# REUN_468349_001_PSU_Board_Connectors.net
KiCad netlist of a schematic drawn in Altium Designer
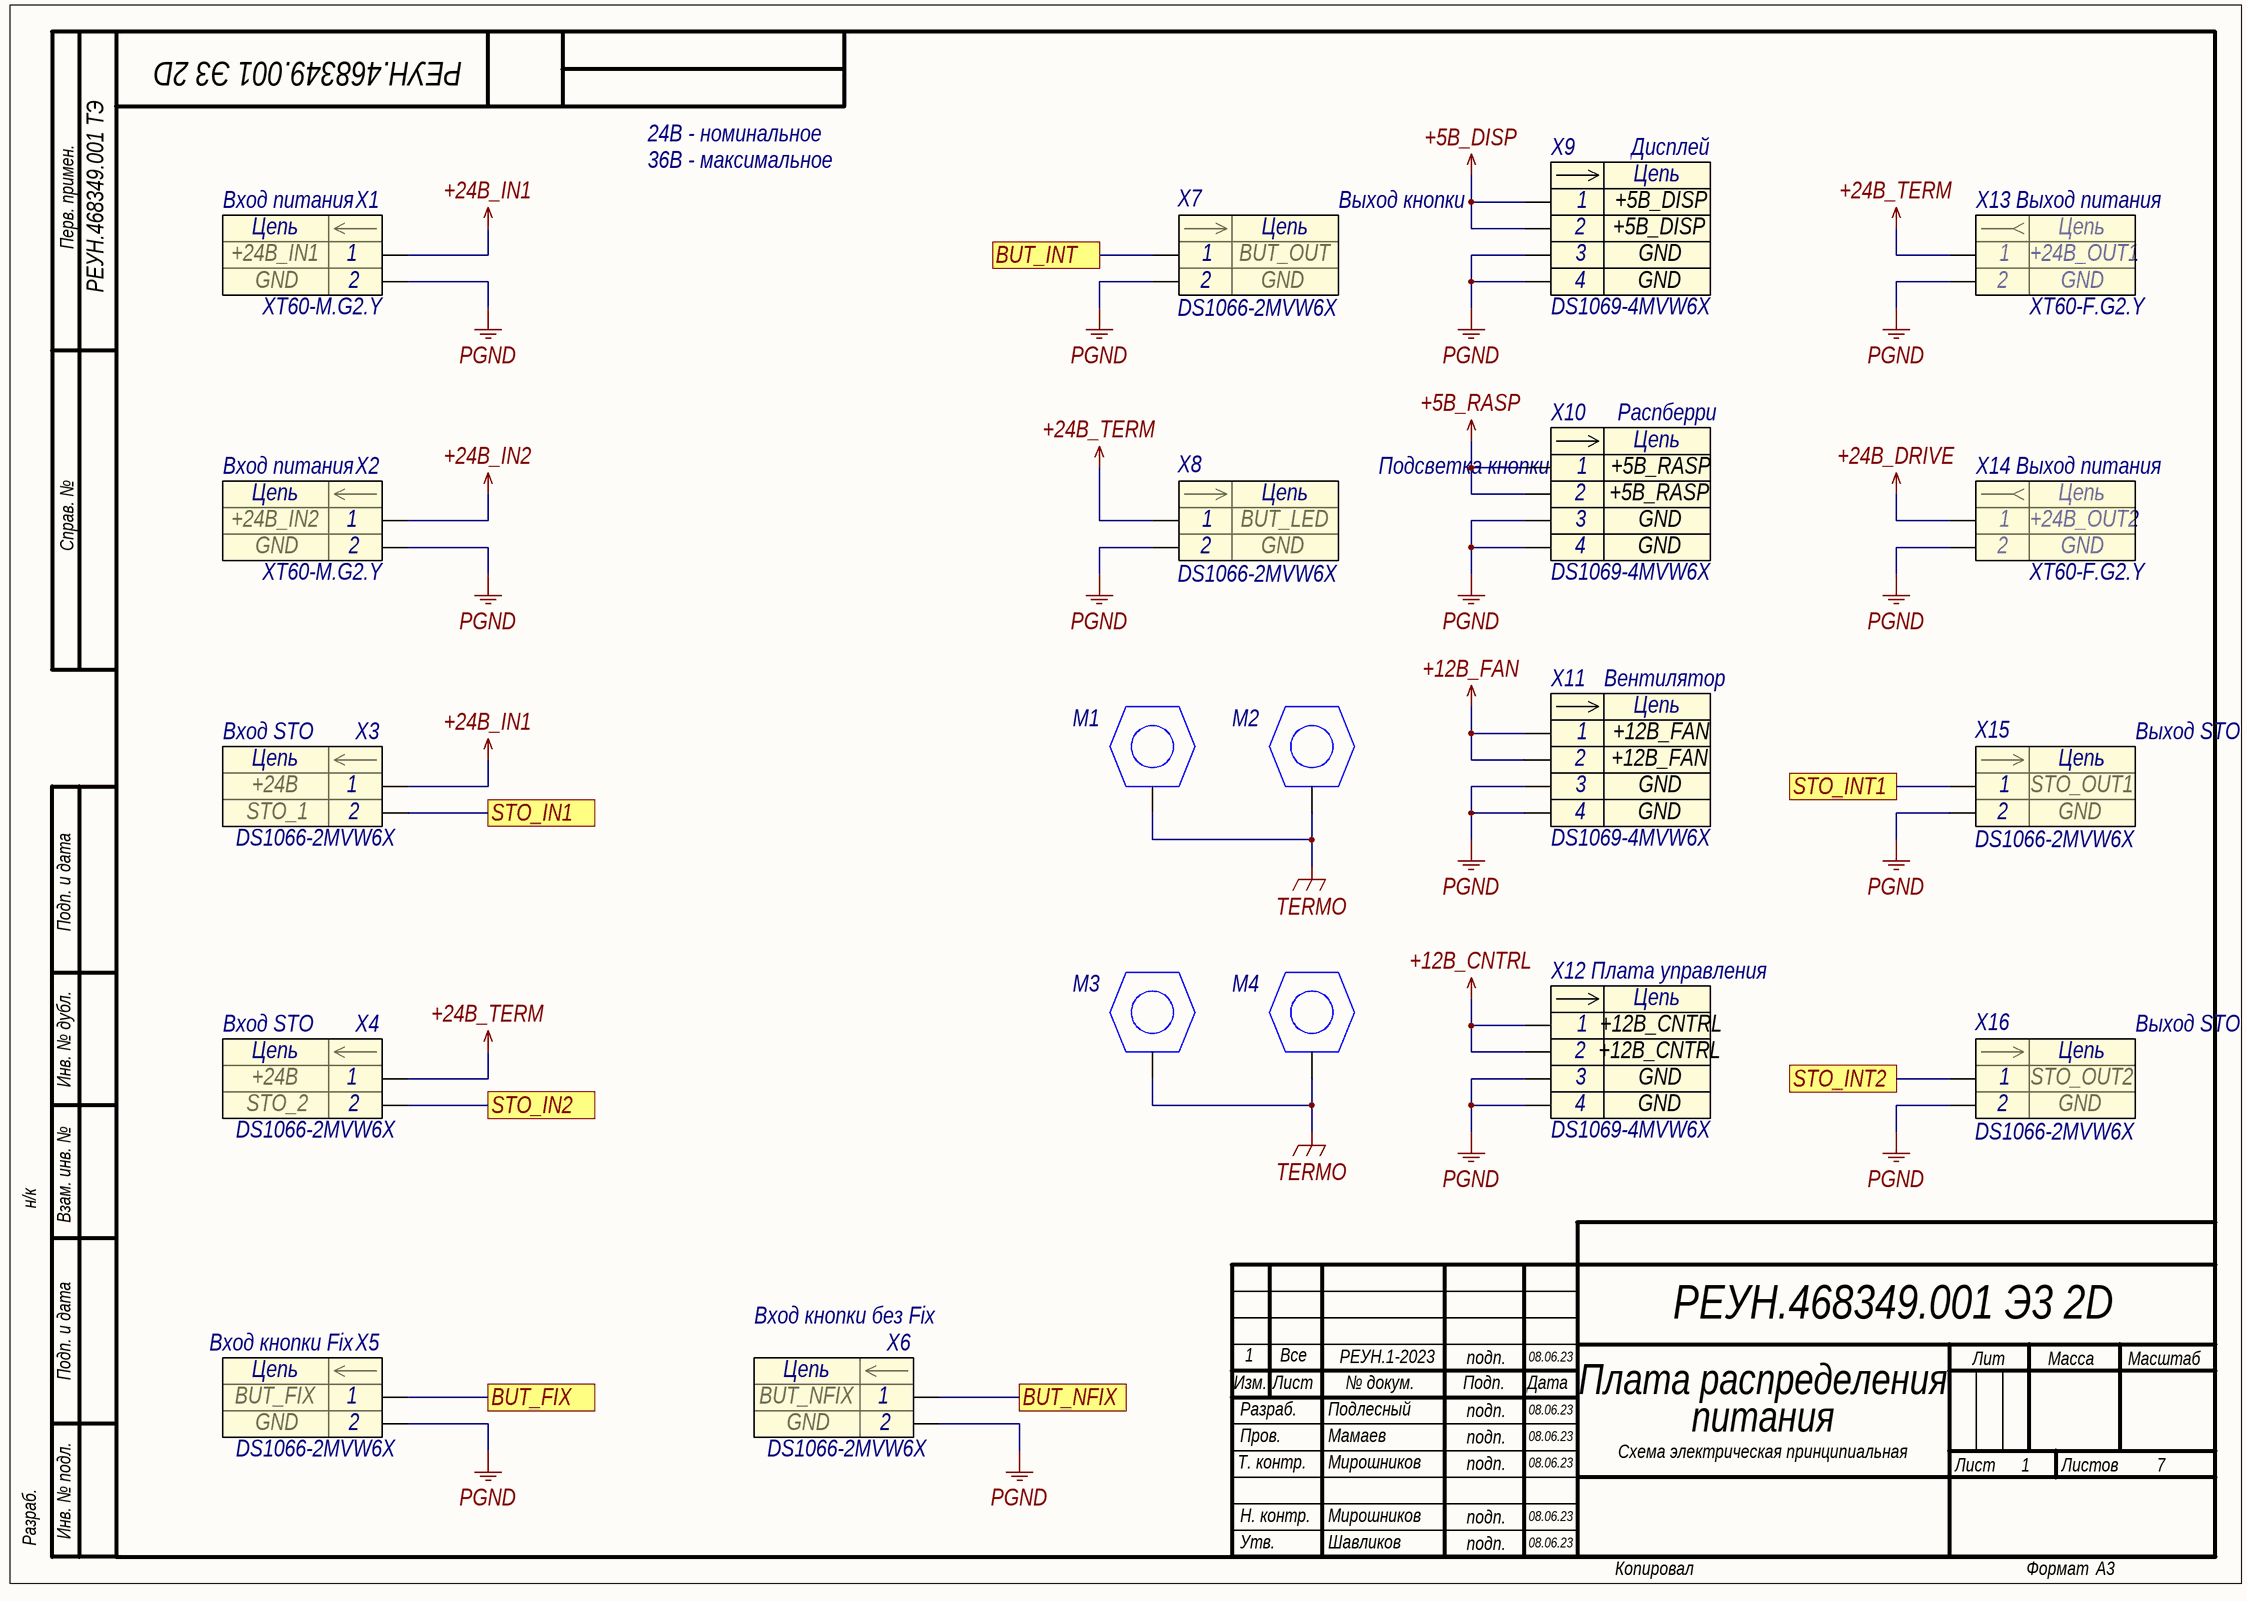
[diagram p0: REUN.468349.001_PSU_Board_Connectors.SchDoc]

(export (version "E")
  (design (tool "Eeschema 10.0.6"))
  (components
    (comp (ref "M1")
      (value "SCREW")
      (footprint "SCREW3.5")
      (libsource (lib "REUN.468349.001_PSU_Board") (part "SCREW"))
    )
    (comp (ref "M2")
      (value "SCREW")
      (footprint "SCREW3.5")
      (libsource (lib "REUN.468349.001_PSU_Board") (part "SCREW"))
    )
    (comp (ref "M3")
      (value "SCREW")
      (footprint "SCREW3.5")
      (libsource (lib "REUN.468349.001_PSU_Board") (part "SCREW"))
    )
    (comp (ref "M4")
      (value "SCREW")
      (footprint "SCREW3.5")
      (libsource (lib "REUN.468349.001_PSU_Board") (part "SCREW"))
    )
    (comp (ref "X1")
      (value "XT60-M.G2.Y")
      (footprint "XT60-M_TH")
      (description "Разъем - 2 конт. вилка")
      (libsource (lib "MOP44") (part "Header_2_plg"))
    )
    (comp (ref "X2")
      (value "XT60-M.G2.Y")
      (footprint "XT60-M_TH")
      (description "Разъем - 2 конт. вилка")
      (libsource (lib "MOP44") (part "Header_2_plg"))
    )
    (comp (ref "X3")
      (value "DS1066-2MVW6X")
      (footprint "MW-2M")
      (description "Разъем - 2 конт. вилка")
      (libsource (lib "MOP44") (part "Header_2_plg"))
    )
    (comp (ref "X4")
      (value "DS1066-2MVW6X")
      (footprint "MW-2M")
      (description "Разъем - 2 конт. вилка")
      (libsource (lib "MOP44") (part "Header_2_plg"))
    )
    (comp (ref "X5")
      (value "DS1066-2MVW6X")
      (footprint "MW-2M")
      (description "Разъем - 2 конт. вилка")
      (libsource (lib "MOP44") (part "Header_2_plg"))
    )
    (comp (ref "X6")
      (value "DS1066-2MVW6X")
      (footprint "MW-2M")
      (description "Разъем - 2 конт. вилка")
      (libsource (lib "MOP44") (part "Header_2_plg"))
    )
    (comp (ref "X7")
      (value "DS1066-2MVW6X")
      (footprint "MW-2M")
      (description "Разъем - 2 конт. вилка")
      (libsource (lib "") (part "Header_2_plg_1"))
    )
    (comp (ref "X8")
      (value "DS1066-2MVW6X")
      (footprint "MW-2M")
      (description "Разъем - 2 конт. вилка")
      (libsource (lib "") (part "Header_2_plg_1"))
    )
    (comp (ref "X9")
      (value "DS1069-4MVW6X")
      (footprint "CWF-4")
      (description "Разъем - 4 конт. вилка")
      (fields (field (name "PART NUMBER") "DS1069-4MVW6X"))
      (libsource (lib "MOP44") (part "Header_4_plg"))
    )
    (comp (ref "X10")
      (value "DS1069-4MVW6X")
      (footprint "CWF-4")
      (description "Разъем - 4 конт. вилка")
      (fields (field (name "PART NUMBER") "DS1069-4MVW6X"))
      (libsource (lib "MOP44") (part "Header_4_plg"))
    )
    (comp (ref "X11")
      (value "DS1069-4MVW6X")
      (footprint "CWF-4")
      (description "Разъем - 4 конт. вилка")
      (fields (field (name "PART NUMBER") "DS1069-4MVW6X"))
      (libsource (lib "MOP44") (part "Header_4_plg"))
    )
    (comp (ref "X12")
      (value "DS1069-4MVW6X")
      (footprint "CWF-4")
      (description "Разъем - 4 конт. вилка")
      (fields (field (name "PART NUMBER") "DS1069-4MVW6X"))
      (libsource (lib "MOP44") (part "Header_4_plg"))
    )
    (comp (ref "X13")
      (value "XT60-F.G2.Y")
      (footprint "XT60-F_TH")
      (description "Разъем - 2 конт. розетка")
      (libsource (lib "MOP44") (part "Header_2_sct"))
    )
    (comp (ref "X14")
      (value "XT60-F.G2.Y")
      (footprint "XT60-F_TH")
      (description "Разъем - 2 конт. розетка")
      (libsource (lib "MOP44") (part "Header_2_sct"))
    )
    (comp (ref "X15")
      (value "DS1066-2MVW6X")
      (footprint "MW-2M")
      (description "Разъем - 2 конт. вилка")
      (libsource (lib "") (part "Header_2_plg_1"))
    )
    (comp (ref "X16")
      (value "DS1066-2MVW6X")
      (footprint "MW-2M")
      (description "Разъем - 2 конт. вилка")
      (libsource (lib "") (part "Header_2_plg_1"))
    )
  )
  (nets
    (net (code "1") (name "+5B_DISP") (class "Default")
      (node (ref "X9") (pin "1") (pinfunction "1_1") (pintype "passive"))
      (node (ref "X9") (pin "2") (pinfunction "2_2") (pintype "passive"))
    )
    (net (code "2") (name "+5B_RASP") (class "Default")
      (node (ref "X10") (pin "1") (pinfunction "1_1") (pintype "passive"))
      (node (ref "X10") (pin "2") (pinfunction "2_2") (pintype "passive"))
    )
    (net (code "3") (name "+12B_CNTRL") (class "Default")
      (node (ref "X12") (pin "1") (pinfunction "1_1") (pintype "passive"))
      (node (ref "X12") (pin "2") (pinfunction "2_2") (pintype "passive"))
    )
    (net (code "4") (name "+12B_FAN") (class "Default")
      (node (ref "X11") (pin "1") (pinfunction "1_1") (pintype "passive"))
      (node (ref "X11") (pin "2") (pinfunction "2_2") (pintype "passive"))
    )
    (net (code "5") (name "+24B_DRIVE") (class "Default")
      (node (ref "X14") (pin "1") (pinfunction "1_1") (pintype "passive"))
    )
    (net (code "6") (name "+24B_IN1") (class "Default")
      (node (ref "X1") (pin "1") (pinfunction "1_1") (pintype "passive"))
      (node (ref "X3") (pin "1") (pinfunction "1_1") (pintype "passive"))
    )
    (net (code "7") (name "+24B_IN2") (class "Default")
      (node (ref "X2") (pin "1") (pinfunction "1_1") (pintype "passive"))
    )
    (net (code "8") (name "+24B_TERM") (class "Default")
      (node (ref "X13") (pin "1") (pinfunction "1_1") (pintype "passive"))
      (node (ref "X4") (pin "1") (pinfunction "1_1") (pintype "passive"))
      (node (ref "X8") (pin "1") (pinfunction "1_1") (pintype "passive"))
    )
    (net (code "9") (name "/BUT_FIX") (class "Default")
      (node (ref "X5") (pin "1") (pinfunction "1_1") (pintype "passive"))
    )
    (net (code "10") (name "/BUT_INT") (class "Default")
      (node (ref "X7") (pin "1") (pinfunction "1_1") (pintype "passive"))
    )
    (net (code "11") (name "/BUT_NFIX") (class "Default")
      (node (ref "X6") (pin "1") (pinfunction "1_1") (pintype "passive"))
    )
    (net (code "12") (name "/STO_IN1") (class "Default")
      (node (ref "X3") (pin "2") (pinfunction "2_2") (pintype "passive"))
    )
    (net (code "13") (name "/STO_IN2") (class "Default")
      (node (ref "X4") (pin "2") (pinfunction "2_2") (pintype "passive"))
    )
    (net (code "14") (name "/STO_INT1") (class "Default")
      (node (ref "X15") (pin "1") (pinfunction "1_1") (pintype "passive"))
    )
    (net (code "15") (name "/STO_INT2") (class "Default")
      (node (ref "X16") (pin "1") (pinfunction "1_1") (pintype "passive"))
    )
    (net (code "16") (name "PGND") (class "Default")
      (node (ref "X1") (pin "2") (pinfunction "2_2") (pintype "passive"))
      (node (ref "X10") (pin "3") (pinfunction "3_3") (pintype "passive"))
      (node (ref "X10") (pin "4") (pinfunction "4_4") (pintype "passive"))
      (node (ref "X11") (pin "3") (pinfunction "3_3") (pintype "passive"))
      (node (ref "X11") (pin "4") (pinfunction "4_4") (pintype "passive"))
      (node (ref "X12") (pin "3") (pinfunction "3_3") (pintype "passive"))
      (node (ref "X12") (pin "4") (pinfunction "4_4") (pintype "passive"))
      (node (ref "X13") (pin "2") (pinfunction "2_2") (pintype "passive"))
      (node (ref "X14") (pin "2") (pinfunction "2_2") (pintype "passive"))
      (node (ref "X15") (pin "2") (pinfunction "2_2") (pintype "passive"))
      (node (ref "X16") (pin "2") (pinfunction "2_2") (pintype "passive"))
      (node (ref "X2") (pin "2") (pinfunction "2_2") (pintype "passive"))
      (node (ref "X5") (pin "2") (pinfunction "2_2") (pintype "passive"))
      (node (ref "X6") (pin "2") (pinfunction "2_2") (pintype "passive"))
      (node (ref "X7") (pin "2") (pinfunction "2_2") (pintype "passive"))
      (node (ref "X8") (pin "2") (pinfunction "2_2") (pintype "passive"))
      (node (ref "X9") (pin "3") (pinfunction "3_3") (pintype "passive"))
      (node (ref "X9") (pin "4") (pinfunction "4_4") (pintype "passive"))
    )
    (net (code "17") (name "TERMO") (class "Default")
      (node (ref "M1") (pin "1") (pinfunction "1_1") (pintype "passive"))
      (node (ref "M2") (pin "1") (pinfunction "1_1") (pintype "passive"))
      (node (ref "M3") (pin "1") (pinfunction "1_1") (pintype "passive"))
      (node (ref "M4") (pin "1") (pinfunction "1_1") (pintype "passive"))
    )
  )
)
